# 7segement4minidigits1badidea-mk-1.net
KiCad netlist of a schematic drawn in EAGLE
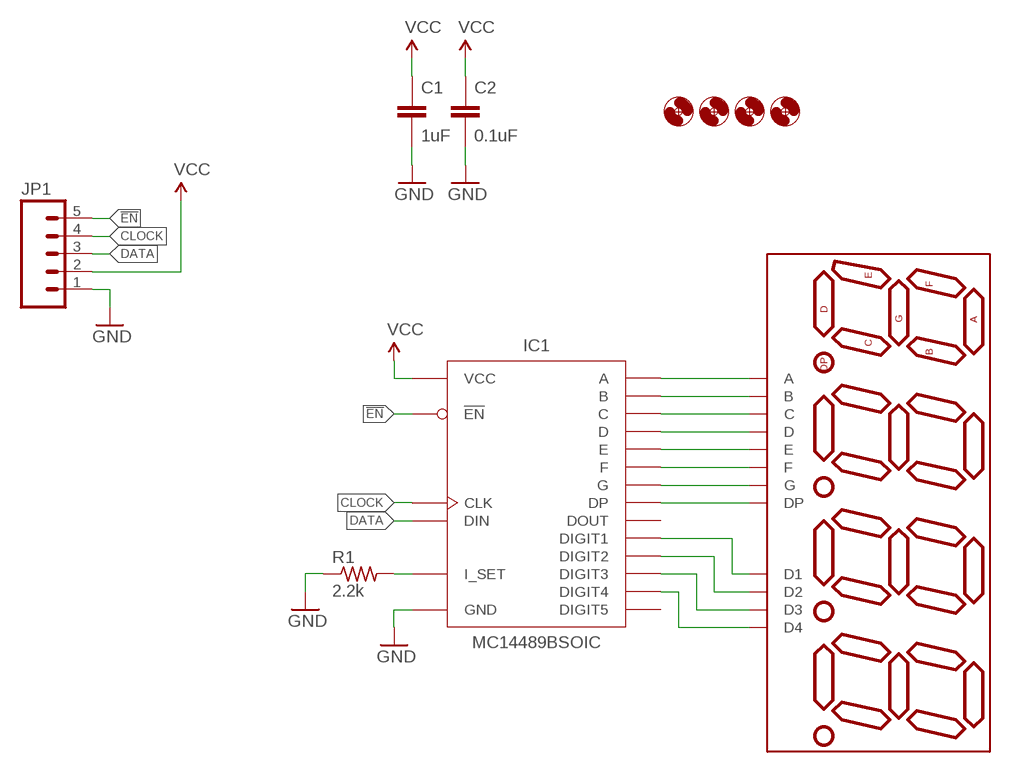
[diagram p0: schematic, sheet 1]

(export (version "E")
  (design (tool "Eeschema 10.0.6"))
  (components
    (comp (ref "C1")
      (value "1uF")
      (footprint "eagle-import:C025-024X044")
      (libsource (lib "eagle-import") (part "CAPACITOR-CERAMIC025-024X044"))
    )
    (comp (ref "C2")
      (value "0.1uF")
      (footprint "eagle-import:C025-024X044")
      (libsource (lib "eagle-import") (part "CAPACITOR-CERAMIC025-024X044"))
    )
    (comp (ref "DISP1")
      (value "BUBBLES!")
      (footprint "eagle-import:DIL12")
      (libsource (lib "eagle-import") (part "7-SEGMENT-4DIGIT-COUNTER-HP-BUBBLE"))
    )
    (comp (ref "H1")
      (value "HOLE#2")
      (footprint "eagle-import:HOLE-#2")
      (libsource (lib "eagle-import") (part "HOLE#2"))
    )
    (comp (ref "H2")
      (value "HOLE#2")
      (footprint "eagle-import:HOLE-#2")
      (libsource (lib "eagle-import") (part "HOLE#2"))
    )
    (comp (ref "H3")
      (value "HOLE#2")
      (footprint "eagle-import:HOLE-#2")
      (libsource (lib "eagle-import") (part "HOLE#2"))
    )
    (comp (ref "H4")
      (value "HOLE#2")
      (footprint "eagle-import:HOLE-#2")
      (libsource (lib "eagle-import") (part "HOLE#2"))
    )
    (comp (ref "IC1")
      (value "MC14489BSOIC")
      (footprint "eagle-import:SOP20W")
      (libsource (lib "eagle-import") (part "MC14489BSOIC"))
    )
    (comp (ref "JP1")
      (value "M05PTH")
      (footprint "eagle-import:1X05")
      (libsource (lib "eagle-import") (part "M05PTH"))
    )
    (comp (ref "R1")
      (value "2.2k")
      (footprint "eagle-import:RESISTOR-AXIAL-PTH-5.08MM")
      (libsource (lib "eagle-import") (part "RESISTORPTH-AXIAL-5.08MM"))
    )
  )
  (nets
    (net (code "1") (name "/~{EN}") (class "Default")
      (node (ref "IC1") (pin "10") (pinfunction "~{EN}_10") (pintype "bidirectional"))
      (node (ref "JP1") (pin "5") (pinfunction "5_5") (pintype "passive"))
    )
    (net (code "2") (name "CLOCK") (class "Default")
      (node (ref "IC1") (pin "11") (pinfunction "CLK_11") (pintype "bidirectional"))
      (node (ref "JP1") (pin "4") (pinfunction "4_4") (pintype "passive"))
    )
    (net (code "3") (name "DATA") (class "Default")
      (node (ref "IC1") (pin "12") (pinfunction "DIN_12") (pintype "bidirectional"))
      (node (ref "JP1") (pin "3") (pinfunction "3_3") (pintype "passive"))
    )
    (net (code "4") (name "GND") (class "Default")
      (node (ref "C1") (pin "2") (pinfunction "2_2") (pintype "passive"))
      (node (ref "C2") (pin "2") (pinfunction "2_2") (pintype "passive"))
      (node (ref "IC1") (pin "14") (pinfunction "GND_14") (pintype "bidirectional"))
      (node (ref "JP1") (pin "1") (pinfunction "1_1") (pintype "passive"))
      (node (ref "R1") (pin "P$1") (pinfunction "1_P$1") (pintype "passive"))
    )
    (net (code "5") (name "Net-(DISP1-A)") (class "Default")
      (node (ref "DISP1") (pin "12") (pinfunction "A_12") (pintype "bidirectional"))
      (node (ref "IC1") (pin "7") (pinfunction "A_7") (pintype "bidirectional"))
    )
    (net (code "6") (name "Net-(DISP1-B)") (class "Default")
      (node (ref "DISP1") (pin "11") (pinfunction "B_11") (pintype "bidirectional"))
      (node (ref "IC1") (pin "6") (pinfunction "B_6") (pintype "bidirectional"))
    )
    (net (code "7") (name "Net-(DISP1-C)") (class "Default")
      (node (ref "DISP1") (pin "3") (pinfunction "C_3") (pintype "bidirectional"))
      (node (ref "IC1") (pin "5") (pinfunction "C_5") (pintype "bidirectional"))
    )
    (net (code "8") (name "Net-(DISP1-D)") (class "Default")
      (node (ref "DISP1") (pin "8") (pinfunction "D_8") (pintype "bidirectional"))
      (node (ref "IC1") (pin "4") (pinfunction "D_4") (pintype "bidirectional"))
    )
    (net (code "9") (name "Net-(DISP1-D1)") (class "Default")
      (node (ref "DISP1") (pin "1") (pinfunction "D1_1") (pintype "bidirectional"))
      (node (ref "IC1") (pin "9") (pinfunction "DIGIT1_9") (pintype "bidirectional"))
    )
    (net (code "10") (name "Net-(DISP1-D2)") (class "Default")
      (node (ref "DISP1") (pin "10") (pinfunction "D2_10") (pintype "bidirectional"))
      (node (ref "IC1") (pin "13") (pinfunction "DIGIT2_13") (pintype "bidirectional"))
    )
    (net (code "11") (name "Net-(DISP1-D3)") (class "Default")
      (node (ref "DISP1") (pin "4") (pinfunction "D3_4") (pintype "bidirectional"))
      (node (ref "IC1") (pin "15") (pinfunction "DIGIT3_15") (pintype "bidirectional"))
    )
    (net (code "12") (name "Net-(DISP1-D4)") (class "Default")
      (node (ref "DISP1") (pin "6") (pinfunction "D4_6") (pintype "bidirectional"))
      (node (ref "IC1") (pin "16") (pinfunction "DIGIT4_16") (pintype "bidirectional"))
    )
    (net (code "13") (name "Net-(DISP1-DP)") (class "Default")
      (node (ref "DISP1") (pin "5") (pinfunction "DP_5") (pintype "bidirectional"))
      (node (ref "IC1") (pin "19") (pinfunction "DP_19") (pintype "bidirectional"))
    )
    (net (code "14") (name "Net-(DISP1-E)") (class "Default")
      (node (ref "DISP1") (pin "2") (pinfunction "E_2") (pintype "bidirectional"))
      (node (ref "IC1") (pin "2") (pinfunction "E_2") (pintype "bidirectional"))
    )
    (net (code "15") (name "Net-(DISP1-F)") (class "Default")
      (node (ref "DISP1") (pin "9") (pinfunction "F_9") (pintype "bidirectional"))
      (node (ref "IC1") (pin "1") (pinfunction "F_1") (pintype "bidirectional"))
    )
    (net (code "16") (name "Net-(DISP1-G)") (class "Default")
      (node (ref "DISP1") (pin "7") (pinfunction "G_7") (pintype "bidirectional"))
      (node (ref "IC1") (pin "20") (pinfunction "G_20") (pintype "bidirectional"))
    )
    (net (code "17") (name "Net-(IC1-I_SET)") (class "Default")
      (node (ref "IC1") (pin "8") (pinfunction "I_SET_8") (pintype "bidirectional"))
      (node (ref "R1") (pin "P$2") (pinfunction "2_P$2") (pintype "passive"))
    )
    (net (code "18") (name "VCC") (class "Default")
      (node (ref "C1") (pin "1") (pinfunction "1_1") (pintype "passive"))
      (node (ref "C2") (pin "1") (pinfunction "1_1") (pintype "passive"))
      (node (ref "IC1") (pin "3") (pinfunction "VCC_3") (pintype "bidirectional"))
      (node (ref "JP1") (pin "2") (pinfunction "2_2") (pintype "passive"))
    )
    (net (code "19") (name "unconnected-(IC1-DIGIT5-Pad17)") (class "Default")
      (node (ref "IC1") (pin "17") (pinfunction "DIGIT5_17") (pintype "bidirectional"))
    )
    (net (code "20") (name "unconnected-(IC1-DOUT-Pad18)") (class "Default")
      (node (ref "IC1") (pin "18") (pinfunction "DOUT_18") (pintype "bidirectional"))
    )
  )
)
